# ecocar_CVM_V2.net
KiCad netlist of a schematic drawn in EAGLE
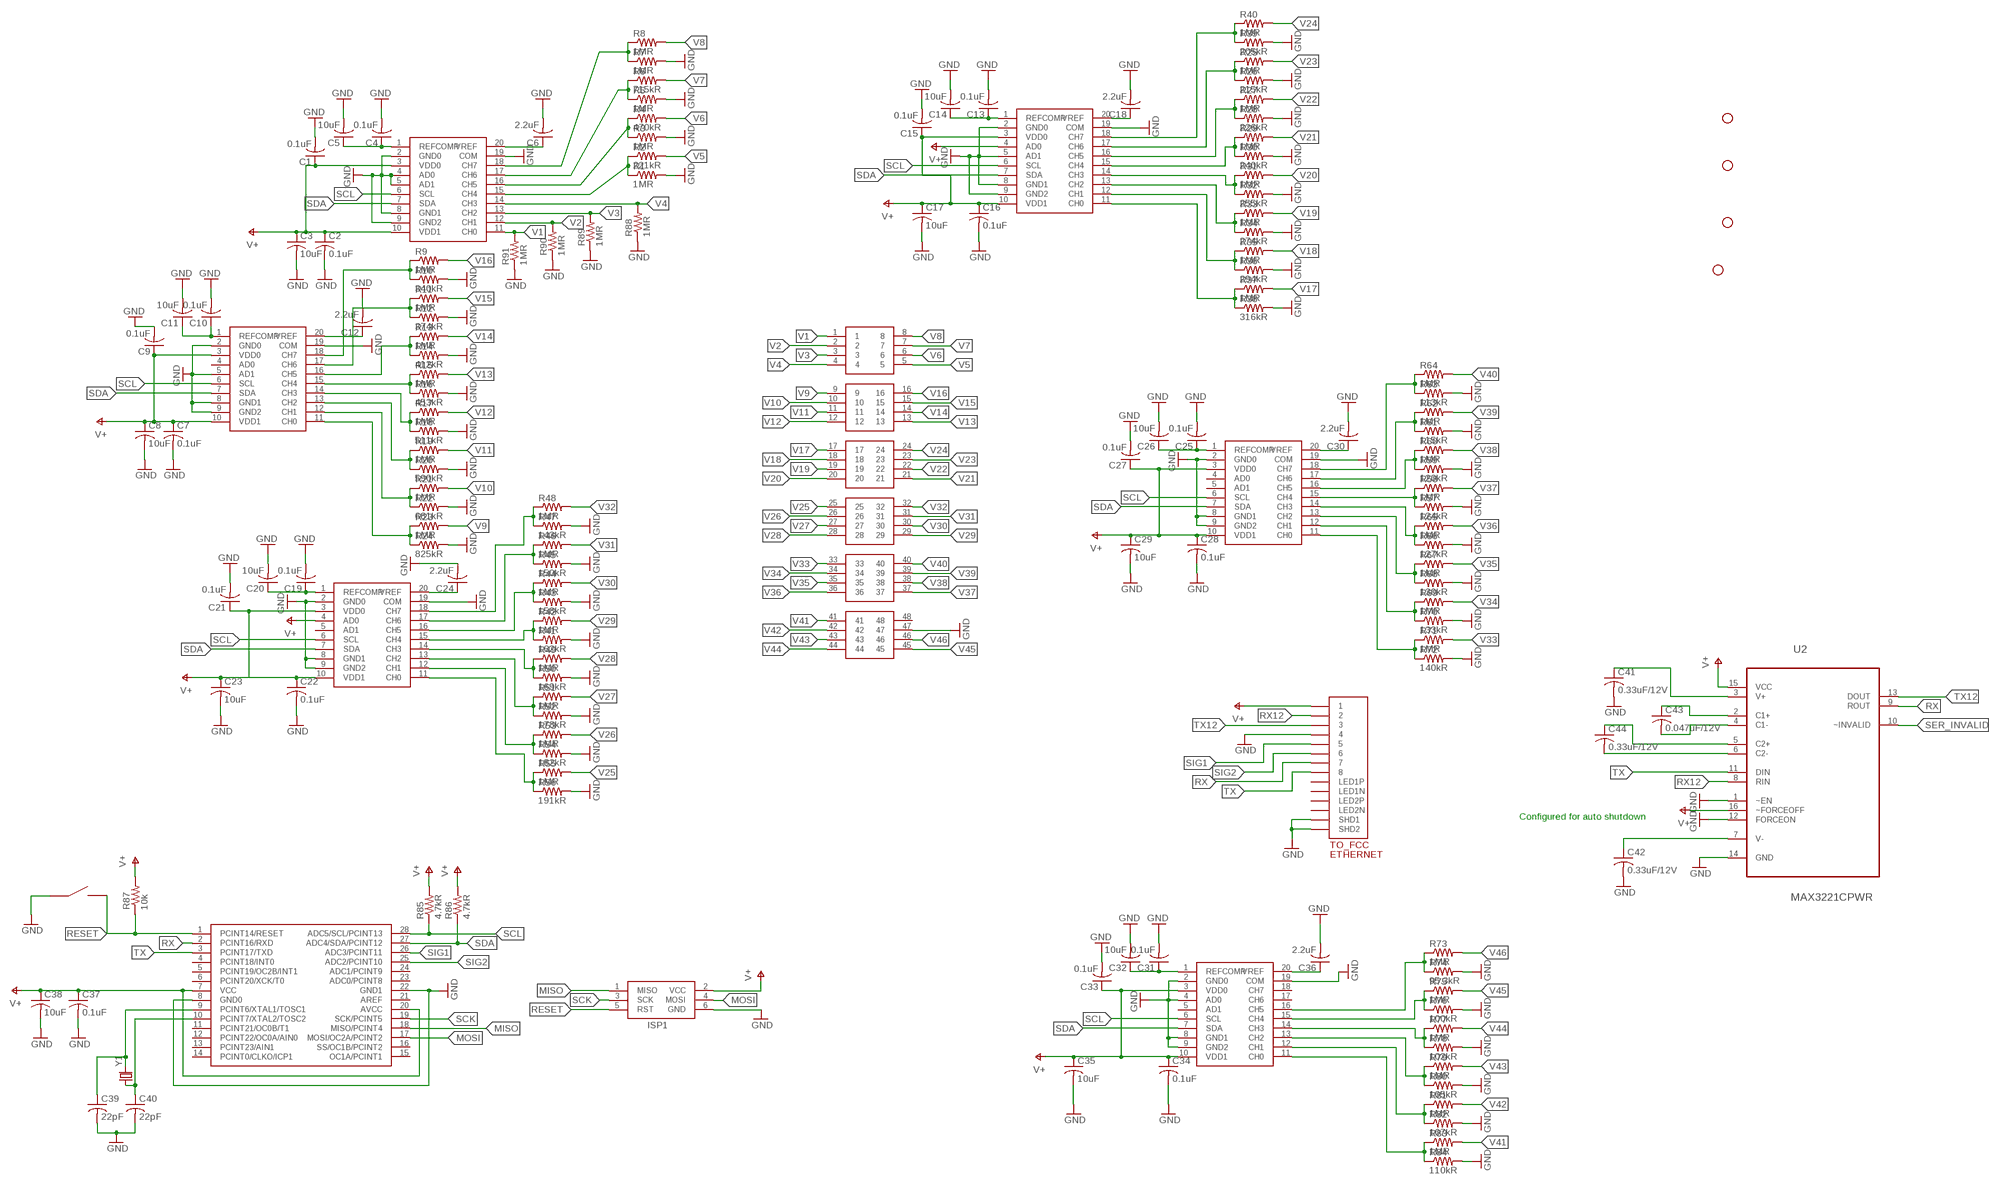
[diagram p0: schematic, sheet 1]

(export (version "E")
  (design (tool "Eeschema 10.0.6"))
  (components
    (comp (ref "0001000")
      (value "LTC2309")
      (footprint "eagle-import:TSSOP20")
      (libsource (lib "eagle-import") (part "LTC2309HF#PBF"))
    )
    (comp (ref "0001001")
      (value "LTC2309")
      (footprint "eagle-import:TSSOP20")
      (libsource (lib "eagle-import") (part "LTC2309HF#PBF"))
    )
    (comp (ref "0001010")
      (value "LTC2309")
      (footprint "eagle-import:TSSOP20")
      (libsource (lib "eagle-import") (part "LTC2309HF#PBF"))
    )
    (comp (ref "0001011")
      (value "LTC2309")
      (footprint "eagle-import:TSSOP20")
      (libsource (lib "eagle-import") (part "LTC2309HF#PBF"))
    )
    (comp (ref "0011000")
      (value "LTC2309")
      (footprint "eagle-import:TSSOP20")
      (libsource (lib "eagle-import") (part "LTC2309HF#PBF"))
    )
    (comp (ref "0011001")
      (value "LTC2309")
      (footprint "eagle-import:TSSOP20")
      (libsource (lib "eagle-import") (part "LTC2309HF#PBF"))
    )
    (comp (ref "C1")
      (value "0.1uF")
      (footprint "eagle-import:C0805")
      (libsource (lib "eagle-import") (part "rcl_C-USC0805"))
    )
    (comp (ref "C2")
      (value "0.1uF")
      (footprint "eagle-import:C0805")
      (libsource (lib "eagle-import") (part "rcl_C-USC0805"))
    )
    (comp (ref "C3")
      (value "10uF")
      (footprint "eagle-import:C0805")
      (libsource (lib "eagle-import") (part "rcl_C-USC0805"))
    )
    (comp (ref "C4")
      (value "0.1uF")
      (footprint "eagle-import:C0805")
      (libsource (lib "eagle-import") (part "rcl_C-USC0805"))
    )
    (comp (ref "C5")
      (value "10uF")
      (footprint "eagle-import:C0805")
      (libsource (lib "eagle-import") (part "rcl_C-USC0805"))
    )
    (comp (ref "C6")
      (value "2.2uF")
      (footprint "eagle-import:C0805")
      (libsource (lib "eagle-import") (part "rcl_C-USC0805"))
    )
    (comp (ref "C7")
      (value "0.1uF")
      (footprint "eagle-import:C0805")
      (libsource (lib "eagle-import") (part "rcl_C-USC0805"))
    )
    (comp (ref "C8")
      (value "10uF")
      (footprint "eagle-import:C0805")
      (libsource (lib "eagle-import") (part "rcl_C-USC0805"))
    )
    (comp (ref "C9")
      (value "0.1uF")
      (footprint "eagle-import:C0805")
      (libsource (lib "eagle-import") (part "rcl_C-USC0805"))
    )
    (comp (ref "C10")
      (value "0.1uF")
      (footprint "eagle-import:C0805")
      (libsource (lib "eagle-import") (part "rcl_C-USC0805"))
    )
    (comp (ref "C11")
      (value "10uF")
      (footprint "eagle-import:C0805")
      (libsource (lib "eagle-import") (part "rcl_C-USC0805"))
    )
    (comp (ref "C12")
      (value "2.2uF")
      (footprint "eagle-import:C0805")
      (libsource (lib "eagle-import") (part "rcl_C-USC0805"))
    )
    (comp (ref "C13")
      (value "0.1uF")
      (footprint "eagle-import:C0805")
      (libsource (lib "eagle-import") (part "rcl_C-USC0805"))
    )
    (comp (ref "C14")
      (value "10uF")
      (footprint "eagle-import:C0805")
      (libsource (lib "eagle-import") (part "rcl_C-USC0805"))
    )
    (comp (ref "C15")
      (value "0.1uF")
      (footprint "eagle-import:C0805")
      (libsource (lib "eagle-import") (part "rcl_C-USC0805"))
    )
    (comp (ref "C16")
      (value "0.1uF")
      (footprint "eagle-import:C0805")
      (libsource (lib "eagle-import") (part "rcl_C-USC0805"))
    )
    (comp (ref "C17")
      (value "10uF")
      (footprint "eagle-import:C0805")
      (libsource (lib "eagle-import") (part "rcl_C-USC0805"))
    )
    (comp (ref "C18")
      (value "2.2uF")
      (footprint "eagle-import:C0805")
      (libsource (lib "eagle-import") (part "rcl_C-USC0805"))
    )
    (comp (ref "C19")
      (value "0.1uF")
      (footprint "eagle-import:C0805")
      (libsource (lib "eagle-import") (part "rcl_C-USC0805"))
    )
    (comp (ref "C20")
      (value "10uF")
      (footprint "eagle-import:C0805")
      (libsource (lib "eagle-import") (part "rcl_C-USC0805"))
    )
    (comp (ref "C21")
      (value "0.1uF")
      (footprint "eagle-import:C0805")
      (libsource (lib "eagle-import") (part "rcl_C-USC0805"))
    )
    (comp (ref "C22")
      (value "0.1uF")
      (footprint "eagle-import:C0805")
      (libsource (lib "eagle-import") (part "rcl_C-USC0805"))
    )
    (comp (ref "C23")
      (value "10uF")
      (footprint "eagle-import:C0805")
      (libsource (lib "eagle-import") (part "rcl_C-USC0805"))
    )
    (comp (ref "C24")
      (value "2.2uF")
      (footprint "eagle-import:C0805")
      (libsource (lib "eagle-import") (part "rcl_C-USC0805"))
    )
    (comp (ref "C25")
      (value "0.1uF")
      (footprint "eagle-import:C0805")
      (libsource (lib "eagle-import") (part "rcl_C-USC0805"))
    )
    (comp (ref "C26")
      (value "10uF")
      (footprint "eagle-import:C0805")
      (libsource (lib "eagle-import") (part "rcl_C-USC0805"))
    )
    (comp (ref "C27")
      (value "0.1uF")
      (footprint "eagle-import:C0805")
      (libsource (lib "eagle-import") (part "rcl_C-USC0805"))
    )
    (comp (ref "C28")
      (value "0.1uF")
      (footprint "eagle-import:C0805")
      (libsource (lib "eagle-import") (part "rcl_C-USC0805"))
    )
    (comp (ref "C29")
      (value "10uF")
      (footprint "eagle-import:C0805")
      (libsource (lib "eagle-import") (part "rcl_C-USC0805"))
    )
    (comp (ref "C30")
      (value "2.2uF")
      (footprint "eagle-import:C0805")
      (libsource (lib "eagle-import") (part "rcl_C-USC0805"))
    )
    (comp (ref "C31")
      (value "0.1uF")
      (footprint "eagle-import:C0805")
      (libsource (lib "eagle-import") (part "rcl_C-USC0805"))
    )
    (comp (ref "C32")
      (value "10uF")
      (footprint "eagle-import:C0805")
      (libsource (lib "eagle-import") (part "rcl_C-USC0805"))
    )
    (comp (ref "C33")
      (value "0.1uF")
      (footprint "eagle-import:C0805")
      (libsource (lib "eagle-import") (part "rcl_C-USC0805"))
    )
    (comp (ref "C34")
      (value "0.1uF")
      (footprint "eagle-import:C0805")
      (libsource (lib "eagle-import") (part "rcl_C-USC0805"))
    )
    (comp (ref "C35")
      (value "10uF")
      (footprint "eagle-import:C0805")
      (libsource (lib "eagle-import") (part "rcl_C-USC0805"))
    )
    (comp (ref "C36")
      (value "2.2uF")
      (footprint "eagle-import:C0805")
      (libsource (lib "eagle-import") (part "rcl_C-USC0805"))
    )
    (comp (ref "C37")
      (value "0.1uF")
      (footprint "eagle-import:C0805")
      (libsource (lib "eagle-import") (part "rcl_C-USC0805"))
    )
    (comp (ref "C38")
      (value "10uF")
      (footprint "eagle-import:C0805")
      (libsource (lib "eagle-import") (part "rcl_C-USC0805"))
    )
    (comp (ref "C39")
      (value "22pF")
      (footprint "eagle-import:C0805")
      (libsource (lib "eagle-import") (part "rcl_C-USC0805"))
    )
    (comp (ref "C40")
      (value "22pF")
      (footprint "eagle-import:C0805")
      (libsource (lib "eagle-import") (part "rcl_C-USC0805"))
    )
    (comp (ref "C41")
      (value "0.33uF/12V")
      (footprint "eagle-import:C0805")
      (libsource (lib "eagle-import") (part "C-USC0805"))
    )
    (comp (ref "C42")
      (value "0.33uF/12V")
      (footprint "eagle-import:C0805")
      (libsource (lib "eagle-import") (part "C-USC0805"))
    )
    (comp (ref "C43")
      (value "0.047uF/12V")
      (footprint "eagle-import:C0805")
      (libsource (lib "eagle-import") (part "C-USC0805"))
    )
    (comp (ref "C44")
      (value "0.33uF/12V")
      (footprint "eagle-import:C0805")
      (libsource (lib "eagle-import") (part "C-USC0805"))
    )
    (comp (ref "ISP1")
      (value "AVRISP-BOX")
      (footprint "eagle-import:AVRISP-BOX")
      (libsource (lib "eagle-import") (part "AVRISP-BOX"))
    )
    (comp (ref "R1")
      (value "1MR")
      (footprint "eagle-import:R0805")
      (libsource (lib "eagle-import") (part "R-US_R0805"))
    )
    (comp (ref "R2")
      (value "221kR")
      (footprint "eagle-import:R0805")
      (libsource (lib "eagle-import") (part "R-US_R0805"))
    )
    (comp (ref "R3")
      (value "1MR")
      (footprint "eagle-import:R0805")
      (libsource (lib "eagle-import") (part "R-US_R0805"))
    )
    (comp (ref "R4")
      (value "470kR")
      (footprint "eagle-import:R0805")
      (libsource (lib "eagle-import") (part "R-US_R0805"))
    )
    (comp (ref "R5")
      (value "1MR")
      (footprint "eagle-import:R0805")
      (libsource (lib "eagle-import") (part "R-US_R0805"))
    )
    (comp (ref "R6")
      (value "715kR")
      (footprint "eagle-import:R0805")
      (libsource (lib "eagle-import") (part "R-US_R0805"))
    )
    (comp (ref "R7")
      (value "1MR")
      (footprint "eagle-import:R0805")
      (libsource (lib "eagle-import") (part "R-US_R0805"))
    )
    (comp (ref "R8")
      (value "1MR")
      (footprint "eagle-import:R0805")
      (libsource (lib "eagle-import") (part "R-US_R0805"))
    )
    (comp (ref "R9")
      (value "1MR")
      (footprint "eagle-import:R0805")
      (libsource (lib "eagle-import") (part "R-US_R0805"))
    )
    (comp (ref "R10")
      (value "340kR")
      (footprint "eagle-import:R0805")
      (libsource (lib "eagle-import") (part "R-US_R0805"))
    )
    (comp (ref "R11")
      (value "1MR")
      (footprint "eagle-import:R0805")
      (libsource (lib "eagle-import") (part "R-US_R0805"))
    )
    (comp (ref "R12")
      (value "374kR")
      (footprint "eagle-import:R0805")
      (libsource (lib "eagle-import") (part "R-US_R0805"))
    )
    (comp (ref "R13")
      (value "1MR")
      (footprint "eagle-import:R0805")
      (libsource (lib "eagle-import") (part "R-US_R0805"))
    )
    (comp (ref "R14")
      (value "412kR")
      (footprint "eagle-import:R0805")
      (libsource (lib "eagle-import") (part "R-US_R0805"))
    )
    (comp (ref "R15")
      (value "1MR")
      (footprint "eagle-import:R0805")
      (libsource (lib "eagle-import") (part "R-US_R0805"))
    )
    (comp (ref "R16")
      (value "453kR")
      (footprint "eagle-import:R0805")
      (libsource (lib "eagle-import") (part "R-US_R0805"))
    )
    (comp (ref "R17")
      (value "1MR")
      (footprint "eagle-import:R0805")
      (libsource (lib "eagle-import") (part "R-US_R0805"))
    )
    (comp (ref "R18")
      (value "511kR")
      (footprint "eagle-import:R0805")
      (libsource (lib "eagle-import") (part "R-US_R0805"))
    )
    (comp (ref "R19")
      (value "1MR")
      (footprint "eagle-import:R0805")
      (libsource (lib "eagle-import") (part "R-US_R0805"))
    )
    (comp (ref "R20")
      (value "590kR")
      (footprint "eagle-import:R0805")
      (libsource (lib "eagle-import") (part "R-US_R0805"))
    )
    (comp (ref "R21")
      (value "1MR")
      (footprint "eagle-import:R0805")
      (libsource (lib "eagle-import") (part "R-US_R0805"))
    )
    (comp (ref "R22")
      (value "681kR")
      (footprint "eagle-import:R0805")
      (libsource (lib "eagle-import") (part "R-US_R0805"))
    )
    (comp (ref "R23")
      (value "1MR")
      (footprint "eagle-import:R0805")
      (libsource (lib "eagle-import") (part "R-US_R0805"))
    )
    (comp (ref "R24")
      (value "825kR")
      (footprint "eagle-import:R0805")
      (libsource (lib "eagle-import") (part "R-US_R0805"))
    )
    (comp (ref "R25")
      (value "1MR")
      (footprint "eagle-import:R0805")
      (libsource (lib "eagle-import") (part "R-US_R0805"))
    )
    (comp (ref "R26")
      (value "215kR")
      (footprint "eagle-import:R0805")
      (libsource (lib "eagle-import") (part "R-US_R0805"))
    )
    (comp (ref "R27")
      (value "1MR")
      (footprint "eagle-import:R0805")
      (libsource (lib "eagle-import") (part "R-US_R0805"))
    )
    (comp (ref "R28")
      (value "226kR")
      (footprint "eagle-import:R0805")
      (libsource (lib "eagle-import") (part "R-US_R0805"))
    )
    (comp (ref "R29")
      (value "1MR")
      (footprint "eagle-import:R0805")
      (libsource (lib "eagle-import") (part "R-US_R0805"))
    )
    (comp (ref "R30")
      (value "240kR")
      (footprint "eagle-import:R0805")
      (libsource (lib "eagle-import") (part "R-US_R0805"))
    )
    (comp (ref "R31")
      (value "1MR")
      (footprint "eagle-import:R0805")
      (libsource (lib "eagle-import") (part "R-US_R0805"))
    )
    (comp (ref "R32")
      (value "255kR")
      (footprint "eagle-import:R0805")
      (libsource (lib "eagle-import") (part "R-US_R0805"))
    )
    (comp (ref "R33")
      (value "1MR")
      (footprint "eagle-import:R0805")
      (libsource (lib "eagle-import") (part "R-US_R0805"))
    )
    (comp (ref "R34")
      (value "274kR")
      (footprint "eagle-import:R0805")
      (libsource (lib "eagle-import") (part "R-US_R0805"))
    )
    (comp (ref "R35")
      (value "1MR")
      (footprint "eagle-import:R0805")
      (libsource (lib "eagle-import") (part "R-US_R0805"))
    )
    (comp (ref "R36")
      (value "294kR")
      (footprint "eagle-import:R0805")
      (libsource (lib "eagle-import") (part "R-US_R0805"))
    )
    (comp (ref "R37")
      (value "1MR")
      (footprint "eagle-import:R0805")
      (libsource (lib "eagle-import") (part "R-US_R0805"))
    )
    (comp (ref "R38")
      (value "316kR")
      (footprint "eagle-import:R0805")
      (libsource (lib "eagle-import") (part "R-US_R0805"))
    )
    (comp (ref "R39")
      (value "205kR")
      (footprint "eagle-import:R0805")
      (libsource (lib "eagle-import") (part "R-US_R0805"))
    )
    (comp (ref "R40")
      (value "1MR")
      (footprint "eagle-import:R0805")
      (libsource (lib "eagle-import") (part "R-US_R0805"))
    )
    (comp (ref "R41")
      (value "162kR")
      (footprint "eagle-import:R0805")
      (libsource (lib "eagle-import") (part "R-US_R0805"))
    )
    (comp (ref "R42")
      (value "1MR")
      (footprint "eagle-import:R0805")
      (libsource (lib "eagle-import") (part "R-US_R0805"))
    )
    (comp (ref "R43")
      (value "158kR")
      (footprint "eagle-import:R0805")
      (libsource (lib "eagle-import") (part "R-US_R0805"))
    )
    (comp (ref "R44")
      (value "1MR")
      (footprint "eagle-import:R0805")
      (libsource (lib "eagle-import") (part "R-US_R0805"))
    )
    (comp (ref "R45")
      (value "150kR")
      (footprint "eagle-import:R0805")
      (libsource (lib "eagle-import") (part "R-US_R0805"))
    )
    (comp (ref "R46")
      (value "1MR")
      (footprint "eagle-import:R0805")
      (libsource (lib "eagle-import") (part "R-US_R0805"))
    )
    (comp (ref "R47")
      (value "143kR")
      (footprint "eagle-import:R0805")
      (libsource (lib "eagle-import") (part "R-US_R0805"))
    )
    (comp (ref "R48")
      (value "1MR")
      (footprint "eagle-import:R0805")
      (libsource (lib "eagle-import") (part "R-US_R0805"))
    )
    (comp (ref "R49")
      (value "1MR")
      (footprint "eagle-import:R0805")
      (libsource (lib "eagle-import") (part "R-US_R0805"))
    )
    (comp (ref "R50")
      (value "169kR")
      (footprint "eagle-import:R0805")
      (libsource (lib "eagle-import") (part "R-US_R0805"))
    )
    (comp (ref "R51")
      (value "1MR")
      (footprint "eagle-import:R0805")
      (libsource (lib "eagle-import") (part "R-US_R0805"))
    )
    (comp (ref "R52")
      (value "178kR")
      (footprint "eagle-import:R0805")
      (libsource (lib "eagle-import") (part "R-US_R0805"))
    )
    (comp (ref "R53")
      (value "1MR")
      (footprint "eagle-import:R0805")
      (libsource (lib "eagle-import") (part "R-US_R0805"))
    )
    (comp (ref "R54")
      (value "182kR")
      (footprint "eagle-import:R0805")
      (libsource (lib "eagle-import") (part "R-US_R0805"))
    )
    (comp (ref "R55")
      (value "1MR")
      (footprint "eagle-import:R0805")
      (libsource (lib "eagle-import") (part "R-US_R0805"))
    )
    (comp (ref "R56")
      (value "191kR")
      (footprint "eagle-import:R0805")
      (libsource (lib "eagle-import") (part "R-US_R0805"))
    )
    (comp (ref "R57")
      (value "124kR")
      (footprint "eagle-import:R0805")
      (libsource (lib "eagle-import") (part "R-US_R0805"))
    )
    (comp (ref "R58")
      (value "1MR")
      (footprint "eagle-import:R0805")
      (libsource (lib "eagle-import") (part "R-US_R0805"))
    )
    (comp (ref "R59")
      (value "120kR")
      (footprint "eagle-import:R0805")
      (libsource (lib "eagle-import") (part "R-US_R0805"))
    )
    (comp (ref "R60")
      (value "1MR")
      (footprint "eagle-import:R0805")
      (libsource (lib "eagle-import") (part "R-US_R0805"))
    )
    (comp (ref "R61")
      (value "115kR")
      (footprint "eagle-import:R0805")
      (libsource (lib "eagle-import") (part "R-US_R0805"))
    )
    (comp (ref "R62")
      (value "1MR")
      (footprint "eagle-import:R0805")
      (libsource (lib "eagle-import") (part "R-US_R0805"))
    )
    (comp (ref "R63")
      (value "113kR")
      (footprint "eagle-import:R0805")
      (libsource (lib "eagle-import") (part "R-US_R0805"))
    )
    (comp (ref "R64")
      (value "1MR")
      (footprint "eagle-import:R0805")
      (libsource (lib "eagle-import") (part "R-US_R0805"))
    )
    (comp (ref "R65")
      (value "1MR")
      (footprint "eagle-import:R0805")
      (libsource (lib "eagle-import") (part "R-US_R0805"))
    )
    (comp (ref "R66")
      (value "127kR")
      (footprint "eagle-import:R0805")
      (libsource (lib "eagle-import") (part "R-US_R0805"))
    )
    (comp (ref "R67")
      (value "1MR")
      (footprint "eagle-import:R0805")
      (libsource (lib "eagle-import") (part "R-US_R0805"))
    )
    (comp (ref "R68")
      (value "130kR")
      (footprint "eagle-import:R0805")
      (libsource (lib "eagle-import") (part "R-US_R0805"))
    )
    (comp (ref "R69")
      (value "1MR")
      (footprint "eagle-import:R0805")
      (libsource (lib "eagle-import") (part "R-US_R0805"))
    )
    (comp (ref "R70")
      (value "133kR")
      (footprint "eagle-import:R0805")
      (libsource (lib "eagle-import") (part "R-US_R0805"))
    )
    (comp (ref "R71")
      (value "1MR")
      (footprint "eagle-import:R0805")
      (libsource (lib "eagle-import") (part "R-US_R0805"))
    )
    (comp (ref "R72")
      (value "140kR")
      (footprint "eagle-import:R0805")
      (libsource (lib "eagle-import") (part "R-US_R0805"))
    )
    (comp (ref "R73")
      (value "1MR")
      (footprint "eagle-import:R0805")
      (libsource (lib "eagle-import") (part "R-US_R0805"))
    )
    (comp (ref "R74")
      (value "95.3kR")
      (footprint "eagle-import:R0805")
      (libsource (lib "eagle-import") (part "R-US_R0805"))
    )
    (comp (ref "R75")
      (value "1MR")
      (footprint "eagle-import:R0805")
      (libsource (lib "eagle-import") (part "R-US_R0805"))
    )
    (comp (ref "R76")
      (value "100kR")
      (footprint "eagle-import:R0805")
      (libsource (lib "eagle-import") (part "R-US_R0805"))
    )
    (comp (ref "R77")
      (value "1MR")
      (footprint "eagle-import:R0805")
      (libsource (lib "eagle-import") (part "R-US_R0805"))
    )
    (comp (ref "R78")
      (value "102kR")
      (footprint "eagle-import:R0805")
      (libsource (lib "eagle-import") (part "R-US_R0805"))
    )
    (comp (ref "R79")
      (value "1MR")
      (footprint "eagle-import:R0805")
      (libsource (lib "eagle-import") (part "R-US_R0805"))
    )
    (comp (ref "R80")
      (value "105kR")
      (footprint "eagle-import:R0805")
      (libsource (lib "eagle-import") (part "R-US_R0805"))
    )
    (comp (ref "R81")
      (value "1MR")
      (footprint "eagle-import:R0805")
      (libsource (lib "eagle-import") (part "R-US_R0805"))
    )
    (comp (ref "R82")
      (value "107kR")
      (footprint "eagle-import:R0805")
      (libsource (lib "eagle-import") (part "R-US_R0805"))
    )
    (comp (ref "R83")
      (value "1MR")
      (footprint "eagle-import:R0805")
      (libsource (lib "eagle-import") (part "R-US_R0805"))
    )
    (comp (ref "R84")
      (value "110kR")
      (footprint "eagle-import:R0805")
      (libsource (lib "eagle-import") (part "R-US_R0805"))
    )
    (comp (ref "R85")
      (value "4.7kR")
      (footprint "eagle-import:R0805")
      (libsource (lib "eagle-import") (part "R-US_R0805"))
    )
    (comp (ref "R86")
      (value "4.7kR")
      (footprint "eagle-import:R0805")
      (libsource (lib "eagle-import") (part "R-US_R0805"))
    )
    (comp (ref "R87")
      (value "10k")
      (footprint "eagle-import:R0805")
      (libsource (lib "eagle-import") (part "R-US_R0805"))
    )
    (comp (ref "R88")
      (value "1MR")
      (footprint "eagle-import:R0805")
      (libsource (lib "eagle-import") (part "R-US_R0805"))
    )
    (comp (ref "R89")
      (value "1MR")
      (footprint "eagle-import:R0805")
      (libsource (lib "eagle-import") (part "R-US_R0805"))
    )
    (comp (ref "R90")
      (value "1MR")
      (footprint "eagle-import:R0805")
      (libsource (lib "eagle-import") (part "R-US_R0805"))
    )
    (comp (ref "R91")
      (value "1MR")
      (footprint "eagle-import:R0805")
      (libsource (lib "eagle-import") (part "R-US_R0805"))
    )
    (comp (ref "RESET_BTN")
      (value "EG4621CT-ND")
      (footprint "eagle-import:EG4621CT-ND")
      (libsource (lib "eagle-import") (part "EG4621CT-ND"))
    )
    (comp (ref "STANDOFF1")
      (value "STAND-OFF")
      (footprint "eagle-import:STAND-OFF")
      (libsource (lib "eagle-import") (part "STAND-OFF"))
    )
    (comp (ref "STANDOFF2")
      (value "STAND-OFF")
      (footprint "eagle-import:STAND-OFF")
      (libsource (lib "eagle-import") (part "STAND-OFF"))
    )
    (comp (ref "STANDOFF3")
      (value "STAND-OFF")
      (footprint "eagle-import:STAND-OFF")
      (libsource (lib "eagle-import") (part "STAND-OFF"))
    )
    (comp (ref "STANDOFF4")
      (value "STAND-OFF")
      (footprint "eagle-import:STAND-OFF")
      (libsource (lib "eagle-import") (part "STAND-OFF"))
    )
    (comp (ref "TO_FCC")
      (value "ETHERNET")
      (footprint "eagle-import:A122645-ND")
      (libsource (lib "eagle-import") (part "ETHERNET"))
    )
    (comp (ref "U$1")
      (value "ATMEGA328P")
      (footprint "eagle-import:DIL28-3")
      (libsource (lib "eagle-import") (part "ATMEGA328P"))
    )
    (comp (ref "U$3")
      (value "6-RJ45")
      (footprint "eagle-import:48-PIN-THROUGHHOLE")
      (libsource (lib "eagle-import") (part "6-RJ45-5557572-3"))
    )
    (comp (ref "U2")
      (value "MAX3221CPWR")
      (footprint "eagle-import:SOP65P640X120-16N")
      (libsource (lib "eagle-import") (part "MAX3221CPWR"))
    )
    (comp (ref "Y1")
      (value "CRYSTALHC49US")
      (footprint "eagle-import:HC49US")
      (libsource (lib "eagle-import") (part "CRYSTALHC49US"))
    )
  )
  (nets
    (net (code "1") (name "GND") (class "Default")
      (node (ref "0001000") (pin "19") (pinfunction "COM_19") (pintype "bidirectional"))
      (node (ref "0001000") (pin "2") (pinfunction "GND0_2") (pintype "bidirectional"))
      (node (ref "0001000") (pin "4") (pinfunction "AD0_4") (pintype "bidirectional"))
      (node (ref "0001000") (pin "5") (pinfunction "AD1_5") (pintype "bidirectional"))
      (node (ref "0001000") (pin "8") (pinfunction "GND1_8") (pintype "bidirectional"))
      (node (ref "0001000") (pin "9") (pinfunction "GND2_9") (pintype "bidirectional"))
      (node (ref "0001001") (pin "19") (pinfunction "COM_19") (pintype "bidirectional"))
      (node (ref "0001001") (pin "2") (pinfunction "GND0_2") (pintype "bidirectional"))
      (node (ref "0001001") (pin "5") (pinfunction "AD1_5") (pintype "bidirectional"))
      (node (ref "0001001") (pin "8") (pinfunction "GND1_8") (pintype "bidirectional"))
      (node (ref "0001001") (pin "9") (pinfunction "GND2_9") (pintype "bidirectional"))
      (node (ref "0001010") (pin "19") (pinfunction "COM_19") (pintype "bidirectional"))
      (node (ref "0001010") (pin "2") (pinfunction "GND0_2") (pintype "bidirectional"))
      (node (ref "0001010") (pin "5") (pinfunction "AD1_5") (pintype "bidirectional"))
      (node (ref "0001010") (pin "8") (pinfunction "GND1_8") (pintype "bidirectional"))
      (node (ref "0001010") (pin "9") (pinfunction "GND2_9") (pintype "bidirectional"))
      (node (ref "0001011") (pin "19") (pinfunction "COM_19") (pintype "bidirectional"))
      (node (ref "0001011") (pin "2") (pinfunction "GND0_2") (pintype "bidirectional"))
      (node (ref "0001011") (pin "8") (pinfunction "GND1_8") (pintype "bidirectional"))
      (node (ref "0001011") (pin "9") (pinfunction "GND2_9") (pintype "bidirectional"))
      (node (ref "0011000") (pin "19") (pinfunction "COM_19") (pintype "bidirectional"))
      (node (ref "0011000") (pin "2") (pinfunction "GND0_2") (pintype "bidirectional"))
      (node (ref "0011000") (pin "8") (pinfunction "GND1_8") (pintype "bidirectional"))
      (node (ref "0011000") (pin "9") (pinfunction "GND2_9") (pintype "bidirectional"))
      (node (ref "0011001") (pin "19") (pinfunction "COM_19") (pintype "bidirectional"))
      (node (ref "0011001") (pin "2") (pinfunction "GND0_2") (pintype "bidirectional"))
      (node (ref "0011001") (pin "4") (pinfunction "AD0_4") (pintype "bidirectional"))
      (node (ref "0011001") (pin "8") (pinfunction "GND1_8") (pintype "bidirectional"))
      (node (ref "0011001") (pin "9") (pinfunction "GND2_9") (pintype "bidirectional"))
      (node (ref "C1") (pin "2") (pinfunction "2_2") (pintype "passive"))
      (node (ref "C10") (pin "2") (pinfunction "2_2") (pintype "passive"))
      (node (ref "C11") (pin "2") (pinfunction "2_2") (pintype "passive"))
      (node (ref "C12") (pin "2") (pinfunction "2_2") (pintype "passive"))
      (node (ref "C13") (pin "2") (pinfunction "2_2") (pintype "passive"))
      (node (ref "C14") (pin "2") (pinfunction "2_2") (pintype "passive"))
      (node (ref "C15") (pin "2") (pinfunction "2_2") (pintype "passive"))
      (node (ref "C16") (pin "2") (pinfunction "2_2") (pintype "passive"))
      (node (ref "C17") (pin "2") (pinfunction "2_2") (pintype "passive"))
      (node (ref "C18") (pin "2") (pinfunction "2_2") (pintype "passive"))
      (node (ref "C19") (pin "2") (pinfunction "2_2") (pintype "passive"))
      (node (ref "C2") (pin "2") (pinfunction "2_2") (pintype "passive"))
      (node (ref "C20") (pin "2") (pinfunction "2_2") (pintype "passive"))
      (node (ref "C21") (pin "2") (pinfunction "2_2") (pintype "passive"))
      (node (ref "C22") (pin "2") (pinfunction "2_2") (pintype "passive"))
      (node (ref "C23") (pin "2") (pinfunction "2_2") (pintype "passive"))
      (node (ref "C24") (pin "2") (pinfunction "2_2") (pintype "passive"))
      (node (ref "C25") (pin "2") (pinfunction "2_2") (pintype "passive"))
      (node (ref "C26") (pin "2") (pinfunction "2_2") (pintype "passive"))
      (node (ref "C27") (pin "2") (pinfunction "2_2") (pintype "passive"))
      (node (ref "C28") (pin "2") (pinfunction "2_2") (pintype "passive"))
      (node (ref "C29") (pin "2") (pinfunction "2_2") (pintype "passive"))
      (node (ref "C3") (pin "2") (pinfunction "2_2") (pintype "passive"))
      (node (ref "C30") (pin "2") (pinfunction "2_2") (pintype "passive"))
      (node (ref "C31") (pin "2") (pinfunction "2_2") (pintype "passive"))
      (node (ref "C32") (pin "2") (pinfunction "2_2") (pintype "passive"))
      (node (ref "C33") (pin "2") (pinfunction "2_2") (pintype "passive"))
      (node (ref "C34") (pin "2") (pinfunction "2_2") (pintype "passive"))
      (node (ref "C35") (pin "2") (pinfunction "2_2") (pintype "passive"))
      (node (ref "C36") (pin "2") (pinfunction "2_2") (pintype "passive"))
      (node (ref "C37") (pin "2") (pinfunction "2_2") (pintype "passive"))
      (node (ref "C38") (pin "2") (pinfunction "2_2") (pintype "passive"))
      (node (ref "C39") (pin "2") (pinfunction "2_2") (pintype "passive"))
      (node (ref "C4") (pin "2") (pinfunction "2_2") (pintype "passive"))
      (node (ref "C40") (pin "2") (pinfunction "2_2") (pintype "passive"))
      (node (ref "C41") (pin "2") (pinfunction "2_2") (pintype "passive"))
      (node (ref "C42") (pin "2") (pinfunction "2_2") (pintype "passive"))
      (node (ref "C5") (pin "2") (pinfunction "2_2") (pintype "passive"))
      (node (ref "C6") (pin "2") (pinfunction "2_2") (pintype "passive"))
      (node (ref "C7") (pin "2") (pinfunction "2_2") (pintype "passive"))
      (node (ref "C8") (pin "2") (pinfunction "2_2") (pintype "passive"))
      (node (ref "C9") (pin "2") (pinfunction "2_2") (pintype "passive"))
      (node (ref "ISP1") (pin "6") (pinfunction "GND_6") (pintype "power_in"))
      (node (ref "R1") (pin "2") (pinfunction "2_2") (pintype "passive"))
      (node (ref "R10") (pin "2") (pinfunction "2_2") (pintype "passive"))
      (node (ref "R12") (pin "2") (pinfunction "2_2") (pintype "passive"))
      (node (ref "R14") (pin "2") (pinfunction "2_2") (pintype "passive"))
      (node (ref "R16") (pin "2") (pinfunction "2_2") (pintype "passive"))
      (node (ref "R18") (pin "2") (pinfunction "2_2") (pintype "passive"))
      (node (ref "R20") (pin "2") (pinfunction "2_2") (pintype "passive"))
      (node (ref "R22") (pin "2") (pinfunction "2_2") (pintype "passive"))
      (node (ref "R24") (pin "2") (pinfunction "2_2") (pintype "passive"))
      (node (ref "R26") (pin "2") (pinfunction "2_2") (pintype "passive"))
      (node (ref "R28") (pin "2") (pinfunction "2_2") (pintype "passive"))
      (node (ref "R3") (pin "2") (pinfunction "2_2") (pintype "passive"))
      (node (ref "R30") (pin "2") (pinfunction "2_2") (pintype "passive"))
      (node (ref "R32") (pin "2") (pinfunction "2_2") (pintype "passive"))
      (node (ref "R34") (pin "2") (pinfunction "2_2") (pintype "passive"))
      (node (ref "R36") (pin "2") (pinfunction "2_2") (pintype "passive"))
      (node (ref "R38") (pin "2") (pinfunction "2_2") (pintype "passive"))
      (node (ref "R39") (pin "2") (pinfunction "2_2") (pintype "passive"))
      (node (ref "R41") (pin "2") (pinfunction "2_2") (pintype "passive"))
      (node (ref "R43") (pin "2") (pinfunction "2_2") (pintype "passive"))
      (node (ref "R45") (pin "2") (pinfunction "2_2") (pintype "passive"))
      (node (ref "R47") (pin "2") (pinfunction "2_2") (pintype "passive"))
      (node (ref "R5") (pin "2") (pinfunction "2_2") (pintype "passive"))
      (node (ref "R50") (pin "2") (pinfunction "2_2") (pintype "passive"))
      (node (ref "R52") (pin "2") (pinfunction "2_2") (pintype "passive"))
      (node (ref "R54") (pin "2") (pinfunction "2_2") (pintype "passive"))
      (node (ref "R56") (pin "2") (pinfunction "2_2") (pintype "passive"))
      (node (ref "R57") (pin "2") (pinfunction "2_2") (pintype "passive"))
      (node (ref "R59") (pin "2") (pinfunction "2_2") (pintype "passive"))
      (node (ref "R61") (pin "2") (pinfunction "2_2") (pintype "passive"))
      (node (ref "R63") (pin "2") (pinfunction "2_2") (pintype "passive"))
      (node (ref "R66") (pin "2") (pinfunction "2_2") (pintype "passive"))
      (node (ref "R68") (pin "2") (pinfunction "2_2") (pintype "passive"))
      (node (ref "R7") (pin "2") (pinfunction "2_2") (pintype "passive"))
      (node (ref "R70") (pin "2") (pinfunction "2_2") (pintype "passive"))
      (node (ref "R72") (pin "2") (pinfunction "2_2") (pintype "passive"))
      (node (ref "R74") (pin "2") (pinfunction "2_2") (pintype "passive"))
      (node (ref "R76") (pin "2") (pinfunction "2_2") (pintype "passive"))
      (node (ref "R78") (pin "2") (pinfunction "2_2") (pintype "passive"))
      (node (ref "R80") (pin "2") (pinfunction "2_2") (pintype "passive"))
      (node (ref "R82") (pin "2") (pinfunction "2_2") (pintype "passive"))
      (node (ref "R84") (pin "2") (pinfunction "2_2") (pintype "passive"))
      (node (ref "R88") (pin "1") (pinfunction "1_1") (pintype "passive"))
      (node (ref "R89") (pin "1") (pinfunction "1_1") (pintype "passive"))
      (node (ref "R90") (pin "1") (pinfunction "1_1") (pintype "passive"))
      (node (ref "R91") (pin "1") (pinfunction "1_1") (pintype "passive"))
      (node (ref "RESET_BTN") (pin "P$1") (pinfunction "P$1_P$1") (pintype "bidirectional"))
      (node (ref "RESET_BTN") (pin "P$2") (pinfunction "P$1_P$2") (pintype "bidirectional"))
      (node (ref "TO_FCC") (pin "P$13") (pinfunction "SHD1_P$13") (pintype "bidirectional"))
      (node (ref "TO_FCC") (pin "P$14") (pinfunction "SHD2_P$14") (pintype "bidirectional"))
      (node (ref "TO_FCC") (pin "P$4") (pinfunction "4_P$4") (pintype "bidirectional"))
      (node (ref "U$1") (pin "22") (pinfunction "GND1_22") (pintype "bidirectional"))
      (node (ref "U$1") (pin "8") (pinfunction "GND0_8") (pintype "bidirectional"))
      (node (ref "U$3") (pin "47") (pinfunction "47_47") (pintype "bidirectional"))
      (node (ref "U2") (pin "1") (pinfunction "~{EN}_1") (pintype "input"))
      (node (ref "U2") (pin "12") (pinfunction "FORCEON_12") (pintype "input"))
      (node (ref "U2") (pin "14") (pinfunction "GND_14") (pintype "passive"))
    )
    (net (code "2") (name "MISO") (class "Default")
      (node (ref "ISP1") (pin "1") (pinfunction "MISO_1") (pintype "input"))
      (node (ref "U$1") (pin "18") (pinfunction "MISO/PCINT4_18") (pintype "bidirectional"))
    )
    (net (code "3") (name "MOSI") (class "Default")
      (node (ref "ISP1") (pin "4") (pinfunction "MOSI_4") (pintype "output"))
      (node (ref "U$1") (pin "17") (pinfunction "MOSI/OC2A/PCINT2_17") (pintype "bidirectional"))
    )
    (net (code "4") (name "Net-(0001000-CH4)") (class "Default")
      (node (ref "0001000") (pin "15") (pinfunction "CH4_15") (pintype "bidirectional"))
      (node (ref "R1") (pin "1") (pinfunction "1_1") (pintype "passive"))
      (node (ref "R2") (pin "1") (pinfunction "1_1") (pintype "passive"))
    )
    (net (code "5") (name "Net-(0001000-CH5)") (class "Default")
      (node (ref "0001000") (pin "16") (pinfunction "CH5_16") (pintype "bidirectional"))
      (node (ref "R3") (pin "1") (pinfunction "1_1") (pintype "passive"))
      (node (ref "R4") (pin "1") (pinfunction "1_1") (pintype "passive"))
    )
    (net (code "6") (name "Net-(0001000-CH6)") (class "Default")
      (node (ref "0001000") (pin "17") (pinfunction "CH6_17") (pintype "bidirectional"))
      (node (ref "R5") (pin "1") (pinfunction "1_1") (pintype "passive"))
      (node (ref "R6") (pin "1") (pinfunction "1_1") (pintype "passive"))
    )
    (net (code "7") (name "Net-(0001000-CH7)") (class "Default")
      (node (ref "0001000") (pin "18") (pinfunction "CH7_18") (pintype "bidirectional"))
      (node (ref "R7") (pin "1") (pinfunction "1_1") (pintype "passive"))
      (node (ref "R8") (pin "1") (pinfunction "1_1") (pintype "passive"))
    )
    (net (code "8") (name "Net-(0001000-REFCOMP)") (class "Default")
      (node (ref "0001000") (pin "1") (pinfunction "REFCOMP_1") (pintype "bidirectional"))
      (node (ref "C4") (pin "1") (pinfunction "1_1") (pintype "passive"))
      (node (ref "C5") (pin "1") (pinfunction "1_1") (pintype "passive"))
    )
    (net (code "9") (name "Net-(0001000-VREF)") (class "Default")
      (node (ref "0001000") (pin "20") (pinfunction "VREF_20") (pintype "bidirectional"))
      (node (ref "C6") (pin "1") (pinfunction "1_1") (pintype "passive"))
    )
    (net (code "10") (name "Net-(0001001-CH0)") (class "Default")
      (node (ref "0001001") (pin "11") (pinfunction "CH0_11") (pintype "bidirectional"))
      (node (ref "R23") (pin "1") (pinfunction "1_1") (pintype "passive"))
      (node (ref "R24") (pin "1") (pinfunction "1_1") (pintype "passive"))
    )
    (net (code "11") (name "Net-(0001001-CH1)") (class "Default")
      (node (ref "0001001") (pin "12") (pinfunction "CH1_12") (pintype "bidirectional"))
      (node (ref "R21") (pin "1") (pinfunction "1_1") (pintype "passive"))
      (node (ref "R22") (pin "1") (pinfunction "1_1") (pintype "passive"))
    )
    (net (code "12") (name "Net-(0001001-CH2)") (class "Default")
      (node (ref "0001001") (pin "13") (pinfunction "CH2_13") (pintype "bidirectional"))
      (node (ref "R19") (pin "1") (pinfunction "1_1") (pintype "passive"))
      (node (ref "R20") (pin "1") (pinfunction "1_1") (pintype "passive"))
    )
    (net (code "13") (name "Net-(0001001-CH3)") (class "Default")
      (node (ref "0001001") (pin "14") (pinfunction "CH3_14") (pintype "bidirectional"))
      (node (ref "R17") (pin "1") (pinfunction "1_1") (pintype "passive"))
      (node (ref "R18") (pin "1") (pinfunction "1_1") (pintype "passive"))
    )
    (net (code "14") (name "Net-(0001001-CH4)") (class "Default")
      (node (ref "0001001") (pin "15") (pinfunction "CH4_15") (pintype "bidirectional"))
      (node (ref "R15") (pin "1") (pinfunction "1_1") (pintype "passive"))
      (node (ref "R16") (pin "1") (pinfunction "1_1") (pintype "passive"))
    )
    (net (code "15") (name "Net-(0001001-CH5)") (class "Default")
      (node (ref "0001001") (pin "16") (pinfunction "CH5_16") (pintype "bidirectional"))
      (node (ref "R13") (pin "1") (pinfunction "1_1") (pintype "passive"))
      (node (ref "R14") (pin "1") (pinfunction "1_1") (pintype "passive"))
    )
    (net (code "16") (name "Net-(0001001-CH6)") (class "Default")
      (node (ref "0001001") (pin "17") (pinfunction "CH6_17") (pintype "bidirectional"))
      (node (ref "R11") (pin "1") (pinfunction "1_1") (pintype "passive"))
      (node (ref "R12") (pin "1") (pinfunction "1_1") (pintype "passive"))
    )
    (net (code "17") (name "Net-(0001001-CH7)") (class "Default")
      (node (ref "0001001") (pin "18") (pinfunction "CH7_18") (pintype "bidirectional"))
      (node (ref "R10") (pin "1") (pinfunction "1_1") (pintype "passive"))
      (node (ref "R9") (pin "1") (pinfunction "1_1") (pintype "passive"))
    )
    (net (code "18") (name "Net-(0001001-REFCOMP)") (class "Default")
      (node (ref "0001001") (pin "1") (pinfunction "REFCOMP_1") (pintype "bidirectional"))
      (node (ref "C10") (pin "1") (pinfunction "1_1") (pintype "passive"))
      (node (ref "C11") (pin "1") (pinfunction "1_1") (pintype "passive"))
    )
    (net (code "19") (name "Net-(0001001-VREF)") (class "Default")
      (node (ref "0001001") (pin "20") (pinfunction "VREF_20") (pintype "bidirectional"))
      (node (ref "C12") (pin "1") (pinfunction "1_1") (pintype "passive"))
    )
    (net (code "20") (name "Net-(0001010-CH0)") (class "Default")
      (node (ref "0001010") (pin "11") (pinfunction "CH0_11") (pintype "bidirectional"))
      (node (ref "R37") (pin "1") (pinfunction "1_1") (pintype "passive"))
      (node (ref "R38") (pin "1") (pinfunction "1_1") (pintype "passive"))
    )
    (net (code "21") (name "Net-(0001010-CH1)") (class "Default")
      (node (ref "0001010") (pin "12") (pinfunction "CH1_12") (pintype "bidirectional"))
      (node (ref "R35") (pin "1") (pinfunction "1_1") (pintype "passive"))
      (node (ref "R36") (pin "1") (pinfunction "1_1") (pintype "passive"))
    )
    (net (code "22") (name "Net-(0001010-CH2)") (class "Default")
      (node (ref "0001010") (pin "13") (pinfunction "CH2_13") (pintype "bidirectional"))
      (node (ref "R33") (pin "1") (pinfunction "1_1") (pintype "passive"))
      (node (ref "R34") (pin "1") (pinfunction "1_1") (pintype "passive"))
    )
    (net (code "23") (name "Net-(0001010-CH3)") (class "Default")
      (node (ref "0001010") (pin "14") (pinfunction "CH3_14") (pintype "bidirectional"))
      (node (ref "R31") (pin "1") (pinfunction "1_1") (pintype "passive"))
      (node (ref "R32") (pin "1") (pinfunction "1_1") (pintype "passive"))
    )
    (net (code "24") (name "Net-(0001010-CH4)") (class "Default")
      (node (ref "0001010") (pin "15") (pinfunction "CH4_15") (pintype "bidirectional"))
      (node (ref "R29") (pin "1") (pinfunction "1_1") (pintype "passive"))
      (node (ref "R30") (pin "1") (pinfunction "1_1") (pintype "passive"))
    )
    (net (code "25") (name "Net-(0001010-CH5)") (class "Default")
      (node (ref "0001010") (pin "16") (pinfunction "CH5_16") (pintype "bidirectional"))
      (node (ref "R27") (pin "1") (pinfunction "1_1") (pintype "passive"))
      (node (ref "R28") (pin "1") (pinfunction "1_1") (pintype "passive"))
    )
    (net (code "26") (name "Net-(0001010-CH6)") (class "Default")
      (node (ref "0001010") (pin "17") (pinfunction "CH6_17") (pintype "bidirectional"))
      (node (ref "R25") (pin "1") (pinfunction "1_1") (pintype "passive"))
      (node (ref "R26") (pin "1") (pinfunction "1_1") (pintype "passive"))
    )
    (net (code "27") (name "Net-(0001010-CH7)") (class "Default")
      (node (ref "0001010") (pin "18") (pinfunction "CH7_18") (pintype "bidirectional"))
      (node (ref "R39") (pin "1") (pinfunction "1_1") (pintype "passive"))
      (node (ref "R40") (pin "1") (pinfunction "1_1") (pintype "passive"))
    )
    (net (code "28") (name "Net-(0001010-REFCOMP)") (class "Default")
      (node (ref "0001010") (pin "1") (pinfunction "REFCOMP_1") (pintype "bidirectional"))
      (node (ref "C13") (pin "1") (pinfunction "1_1") (pintype "passive"))
      (node (ref "C14") (pin "1") (pinfunction "1_1") (pintype "passive"))
    )
    (net (code "29") (name "Net-(0001010-VREF)") (class "Default")
      (node (ref "0001010") (pin "20") (pinfunction "VREF_20") (pintype "bidirectional"))
      (node (ref "C18") (pin "1") (pinfunction "1_1") (pintype "passive"))
    )
    (net (code "30") (name "Net-(0001011-CH0)") (class "Default")
      (node (ref "0001011") (pin "11") (pinfunction "CH0_11") (pintype "bidirectional"))
      (node (ref "R55") (pin "1") (pinfunction "1_1") (pintype "passive"))
      (node (ref "R56") (pin "1") (pinfunction "1_1") (pintype "passive"))
    )
    (net (code "31") (name "Net-(0001011-CH1)") (class "Default")
      (node (ref "0001011") (pin "12") (pinfunction "CH1_12") (pintype "bidirectional"))
      (node (ref "R53") (pin "1") (pinfunction "1_1") (pintype "passive"))
      (node (ref "R54") (pin "1") (pinfunction "1_1") (pintype "passive"))
    )
    (net (code "32") (name "Net-(0001011-CH2)") (class "Default")
      (node (ref "0001011") (pin "13") (pinfunction "CH2_13") (pintype "bidirectional"))
      (node (ref "R51") (pin "1") (pinfunction "1_1") (pintype "passive"))
      (node (ref "R52") (pin "1") (pinfunction "1_1") (pintype "passive"))
    )
    (net (code "33") (name "Net-(0001011-CH3)") (class "Default")
      (node (ref "0001011") (pin "14") (pinfunction "CH3_14") (pintype "bidirectional"))
      (node (ref "R49") (pin "1") (pinfunction "1_1") (pintype "passive"))
      (node (ref "R50") (pin "1") (pinfunction "1_1") (pintype "passive"))
    )
    (net (code "34") (name "Net-(0001011-CH4)") (class "Default")
      (node (ref "0001011") (pin "15") (pinfunction "CH4_15") (pintype "bidirectional"))
      (node (ref "R41") (pin "1") (pinfunction "1_1") (pintype "passive"))
      (node (ref "R42") (pin "1") (pinfunction "1_1") (pintype "passive"))
    )
    (net (code "35") (name "Net-(0001011-CH5)") (class "Default")
      (node (ref "0001011") (pin "16") (pinfunction "CH5_16") (pintype "bidirectional"))
      (node (ref "R43") (pin "1") (pinfunction "1_1") (pintype "passive"))
      (node (ref "R44") (pin "1") (pinfunction "1_1") (pintype "passive"))
    )
    (net (code "36") (name "Net-(0001011-CH6)") (class "Default")
      (node (ref "0001011") (pin "17") (pinfunction "CH6_17") (pintype "bidirectional"))
      (node (ref "R45") (pin "1") (pinfunction "1_1") (pintype "passive"))
      (node (ref "R46") (pin "1") (pinfunction "1_1") (pintype "passive"))
    )
    (net (code "37") (name "Net-(0001011-CH7)") (class "Default")
      (node (ref "0001011") (pin "18") (pinfunction "CH7_18") (pintype "bidirectional"))
      (node (ref "R47") (pin "1") (pinfunction "1_1") (pintype "passive"))
      (node (ref "R48") (pin "1") (pinfunction "1_1") (pintype "passive"))
    )
    (net (code "38") (name "Net-(0001011-REFCOMP)") (class "Default")
      (node (ref "0001011") (pin "1") (pinfunction "REFCOMP_1") (pintype "bidirectional"))
      (node (ref "C19") (pin "1") (pinfunction "1_1") (pintype "passive"))
      (node (ref "C20") (pin "1") (pinfunction "1_1") (pintype "passive"))
    )
    (net (code "39") (name "Net-(0001011-VREF)") (class "Default")
      (node (ref "0001011") (pin "20") (pinfunction "VREF_20") (pintype "bidirectional"))
      (node (ref "C24") (pin "1") (pinfunction "1_1") (pintype "passive"))
    )
    (net (code "40") (name "Net-(0011000-CH0)") (class "Default")
      (node (ref "0011000") (pin "11") (pinfunction "CH0_11") (pintype "bidirectional"))
      (node (ref "R71") (pin "1") (pinfunction "1_1") (pintype "passive"))
      (node (ref "R72") (pin "1") (pinfunction "1_1") (pintype "passive"))
    )
    (net (code "41") (name "Net-(0011000-CH1)") (class "Default")
      (node (ref "0011000") (pin "12") (pinfunction "CH1_12") (pintype "bidirectional"))
      (node (ref "R69") (pin "1") (pinfunction "1_1") (pintype "passive"))
      (node (ref "R70") (pin "1") (pinfunction "1_1") (pintype "passive"))
    )
    (net (code "42") (name "Net-(0011000-CH2)") (class "Default")
      (node (ref "0011000") (pin "13") (pinfunction "CH2_13") (pintype "bidirectional"))
      (node (ref "R67") (pin "1") (pinfunction "1_1") (pintype "passive"))
      (node (ref "R68") (pin "1") (pinfunction "1_1") (pintype "passive"))
    )
    (net (code "43") (name "Net-(0011000-CH3)") (class "Default")
      (node (ref "0011000") (pin "14") (pinfunction "CH3_14") (pintype "bidirectional"))
      (node (ref "R65") (pin "1") (pinfunction "1_1") (pintype "passive"))
      (node (ref "R66") (pin "1") (pinfunction "1_1") (pintype "passive"))
    )
    (net (code "44") (name "Net-(0011000-CH4)") (class "Default")
      (node (ref "0011000") (pin "15") (pinfunction "CH4_15") (pintype "bidirectional"))
      (node (ref "R57") (pin "1") (pinfunction "1_1") (pintype "passive"))
      (node (ref "R58") (pin "1") (pinfunction "1_1") (pintype "passive"))
    )
    (net (code "45") (name "Net-(0011000-CH5)") (class "Default")
      (node (ref "0011000") (pin "16") (pinfunction "CH5_16") (pintype "bidirectional"))
      (node (ref "R59") (pin "1") (pinfunction "1_1") (pintype "passive"))
      (node (ref "R60") (pin "1") (pinfunction "1_1") (pintype "passive"))
    )
    (net (code "46") (name "Net-(0011000-CH6)") (class "Default")
      (node (ref "0011000") (pin "17") (pinfunction "CH6_17") (pintype "bidirectional"))
      (node (ref "R61") (pin "1") (pinfunction "1_1") (pintype "passive"))
      (node (ref "R62") (pin "1") (pinfunction "1_1") (pintype "passive"))
    )
    (net (code "47") (name "Net-(0011000-CH7)") (class "Default")
      (node (ref "0011000") (pin "18") (pinfunction "CH7_18") (pintype "bidirectional"))
      (node (ref "R63") (pin "1") (pinfunction "1_1") (pintype "passive"))
      (node (ref "R64") (pin "1") (pinfunction "1_1") (pintype "passive"))
    )
    (net (code "48") (name "Net-(0011000-REFCOMP)") (class "Default")
      (node (ref "0011000") (pin "1") (pinfunction "REFCOMP_1") (pintype "bidirectional"))
      (node (ref "C25") (pin "1") (pinfunction "1_1") (pintype "passive"))
      (node (ref "C26") (pin "1") (pinfunction "1_1") (pintype "passive"))
    )
    (net (code "49") (name "Net-(0011000-VREF)") (class "Default")
      (node (ref "0011000") (pin "20") (pinfunction "VREF_20") (pintype "bidirectional"))
      (node (ref "C30") (pin "1") (pinfunction "1_1") (pintype "passive"))
    )
    (net (code "50") (name "Net-(0011001-CH0)") (class "Default")
      (node (ref "0011001") (pin "11") (pinfunction "CH0_11") (pintype "bidirectional"))
      (node (ref "R83") (pin "1") (pinfunction "1_1") (pintype "passive"))
      (node (ref "R84") (pin "1") (pinfunction "1_1") (pintype "passive"))
    )
    (net (code "51") (name "Net-(0011001-CH1)") (class "Default")
      (node (ref "0011001") (pin "12") (pinfunction "CH1_12") (pintype "bidirectional"))
      (node (ref "R81") (pin "1") (pinfunction "1_1") (pintype "passive"))
      (node (ref "R82") (pin "1") (pinfunction "1_1") (pintype "passive"))
    )
    (net (code "52") (name "Net-(0011001-CH2)") (class "Default")
      (node (ref "0011001") (pin "13") (pinfunction "CH2_13") (pintype "bidirectional"))
      (node (ref "R79") (pin "1") (pinfunction "1_1") (pintype "passive"))
      (node (ref "R80") (pin "1") (pinfunction "1_1") (pintype "passive"))
    )
    (net (code "53") (name "Net-(0011001-CH3)") (class "Default")
      (node (ref "0011001") (pin "14") (pinfunction "CH3_14") (pintype "bidirectional"))
      (node (ref "R77") (pin "1") (pinfunction "1_1") (pintype "passive"))
      (node (ref "R78") (pin "1") (pinfunction "1_1") (pintype "passive"))
    )
    (net (code "54") (name "Net-(0011001-CH4)") (class "Default")
      (node (ref "0011001") (pin "15") (pinfunction "CH4_15") (pintype "bidirectional"))
      (node (ref "R75") (pin "1") (pinfunction "1_1") (pintype "passive"))
      (node (ref "R76") (pin "1") (pinfunction "1_1") (pintype "passive"))
    )
    (net (code "55") (name "Net-(0011001-CH5)") (class "Default")
      (node (ref "0011001") (pin "16") (pinfunction "CH5_16") (pintype "bidirectional"))
      (node (ref "R73") (pin "1") (pinfunction "1_1") (pintype "passive"))
      (node (ref "R74") (pin "1") (pinfunction "1_1") (pintype "passive"))
    )
    (net (code "56") (name "Net-(0011001-REFCOMP)") (class "Default")
      (node (ref "0011001") (pin "1") (pinfunction "REFCOMP_1") (pintype "bidirectional"))
      (node (ref "C31") (pin "1") (pinfunction "1_1") (pintype "passive"))
      (node (ref "C32") (pin "1") (pinfunction "1_1") (pintype "passive"))
    )
    (net (code "57") (name "Net-(0011001-VREF)") (class "Default")
      (node (ref "0011001") (pin "20") (pinfunction "VREF_20") (pintype "bidirectional"))
      (node (ref "C36") (pin "1") (pinfunction "1_1") (pintype "passive"))
    )
    (net (code "58") (name "Net-(U$1-PCINT6{slash}XTAL1{slash}TOSC1)") (class "Default")
      (node (ref "C39") (pin "1") (pinfunction "1_1") (pintype "passive"))
      (node (ref "U$1") (pin "9") (pinfunction "PCINT6/XTAL1/TOSC1_9") (pintype "bidirectional"))
      (node (ref "Y1") (pin "2") (pinfunction "2_2") (pintype "passive"))
    )
    (net (code "59") (name "Net-(U$1-PCINT7{slash}XTAL2{slash}TOSC2)") (class "Default")
      (node (ref "C40") (pin "1") (pinfunction "1_1") (pintype "passive"))
      (node (ref "U$1") (pin "10") (pinfunction "PCINT7/XTAL2/TOSC2_10") (pintype "bidirectional"))
      (node (ref "Y1") (pin "1") (pinfunction "1_1") (pintype "passive"))
    )
    (net (code "60") (name "Net-(U2-C1+)") (class "Default")
      (node (ref "C43") (pin "1") (pinfunction "1_1") (pintype "passive"))
      (node (ref "U2") (pin "2") (pinfunction "C1+_2") (pintype "passive"))
    )
    (net (code "61") (name "Net-(U2-C1-)") (class "Default")
      (node (ref "C43") (pin "2") (pinfunction "2_2") (pintype "passive"))
      (node (ref "U2") (pin "4") (pinfunction "C1-_4") (pintype "passive"))
    )
    (net (code "62") (name "Net-(U2-C2+)") (class "Default")
      (node (ref "C44") (pin "1") (pinfunction "1_1") (pintype "passive"))
      (node (ref "U2") (pin "5") (pinfunction "C2+_5") (pintype "passive"))
    )
    (net (code "63") (name "Net-(U2-C2-)") (class "Default")
      (node (ref "C44") (pin "2") (pinfunction "2_2") (pintype "passive"))
      (node (ref "U2") (pin "6") (pinfunction "C2-_6") (pintype "passive"))
    )
    (net (code "64") (name "Net-(U2-V+)") (class "Default")
      (node (ref "C41") (pin "1") (pinfunction "1_1") (pintype "passive"))
      (node (ref "U2") (pin "3") (pinfunction "V+_3") (pintype "power_in"))
    )
    (net (code "65") (name "Net-(U2-V-)") (class "Default")
      (node (ref "C42") (pin "1") (pinfunction "1_1") (pintype "passive"))
      (node (ref "U2") (pin "7") (pinfunction "V-_7") (pintype "power_in"))
    )
    (net (code "66") (name "RESET") (class "Default")
      (node (ref "ISP1") (pin "5") (pinfunction "RST_5") (pintype "output"))
      (node (ref "R87") (pin "1") (pinfunction "1_1") (pintype "passive"))
      (node (ref "RESET_BTN") (pin "P$3") (pinfunction "P$2_P$3") (pintype "bidirectional"))
      (node (ref "RESET_BTN") (pin "P$4") (pinfunction "P$2_P$4") (pintype "bidirectional"))
      (node (ref "U$1") (pin "1") (pinfunction "PCINT14/RESET_1") (pintype "bidirectional"))
    )
    (net (code "67") (name "RX") (class "Default")
      (node (ref "TO_FCC") (pin "P$7") (pinfunction "7_P$7") (pintype "bidirectional"))
      (node (ref "U$1") (pin "2") (pinfunction "PCINT16/RXD_2") (pintype "bidirectional"))
      (node (ref "U2") (pin "9") (pinfunction "ROUT_9") (pintype "output"))
    )
    (net (code "68") (name "RX12") (class "Default")
      (node (ref "TO_FCC") (pin "P$2") (pinfunction "2_P$2") (pintype "bidirectional"))
      (node (ref "U2") (pin "8") (pinfunction "RIN_8") (pintype "input"))
    )
    (net (code "69") (name "SCK") (class "Default")
      (node (ref "ISP1") (pin "3") (pinfunction "SCK_3") (pintype "output"))
      (node (ref "U$1") (pin "19") (pinfunction "SCK/PCINT5_19") (pintype "bidirectional"))
    )
    (net (code "70") (name "SCL") (class "Default")
      (node (ref "0001000") (pin "6") (pinfunction "SCL_6") (pintype "bidirectional"))
      (node (ref "0001001") (pin "6") (pinfunction "SCL_6") (pintype "bidirectional"))
      (node (ref "0001010") (pin "6") (pinfunction "SCL_6") (pintype "bidirectional"))
      (node (ref "0001011") (pin "6") (pinfunction "SCL_6") (pintype "bidirectional"))
      (node (ref "0011000") (pin "6") (pinfunction "SCL_6") (pintype "bidirectional"))
      (node (ref "0011001") (pin "6") (pinfunction "SCL_6") (pintype "bidirectional"))
      (node (ref "R85") (pin "1") (pinfunction "1_1") (pintype "passive"))
      (node (ref "U$1") (pin "28") (pinfunction "ADC5/SCL/PCINT13_28") (pintype "bidirectional"))
    )
    (net (code "71") (name "SDA") (class "Default")
      (node (ref "0001000") (pin "7") (pinfunction "SDA_7") (pintype "bidirectional"))
      (node (ref "0001001") (pin "7") (pinfunction "SDA_7") (pintype "bidirectional"))
      (node (ref "0001010") (pin "7") (pinfunction "SDA_7") (pintype "bidirectional"))
      (node (ref "0001011") (pin "7") (pinfunction "SDA_7") (pintype "bidirectional"))
      (node (ref "0011000") (pin "7") (pinfunction "SDA_7") (pintype "bidirectional"))
      (node (ref "0011001") (pin "7") (pinfunction "SDA_7") (pintype "bidirectional"))
      (node (ref "R86") (pin "1") (pinfunction "1_1") (pintype "passive"))
      (node (ref "U$1") (pin "27") (pinfunction "ADC4/SDA/PCINT12_27") (pintype "bidirectional"))
    )
    (net (code "72") (name "SER_INVALID") (class "Default")
      (node (ref "U2") (pin "10") (pinfunction "~{INVALID}_10") (pintype "output"))
    )
    (net (code "73") (name "SIG1") (class "Default")
      (node (ref "TO_FCC") (pin "P$5") (pinfunction "5_P$5") (pintype "bidirectional"))
      (node (ref "U$1") (pin "26") (pinfunction "ADC3/PCINT11_26") (pintype "bidirectional"))
    )
    (net (code "74") (name "SIG2") (class "Default")
      (node (ref "TO_FCC") (pin "P$6") (pinfunction "6_P$6") (pintype "bidirectional"))
      (node (ref "U$1") (pin "25") (pinfunction "ADC2/PCINT10_25") (pintype "bidirectional"))
    )
    (net (code "75") (name "TX") (class "Default")
      (node (ref "TO_FCC") (pin "P$8") (pinfunction "8_P$8") (pintype "bidirectional"))
      (node (ref "U$1") (pin "3") (pinfunction "PCINT17/TXD_3") (pintype "bidirectional"))
      (node (ref "U2") (pin "11") (pinfunction "DIN_11") (pintype "input"))
    )
    (net (code "76") (name "TX12") (class "Default")
      (node (ref "TO_FCC") (pin "P$3") (pinfunction "3_P$3") (pintype "bidirectional"))
      (node (ref "U2") (pin "13") (pinfunction "DOUT_13") (pintype "output"))
    )
    (net (code "77") (name "V+") (class "Default")
      (node (ref "0001000") (pin "10") (pinfunction "VDD1_10") (pintype "bidirectional"))
      (node (ref "0001000") (pin "3") (pinfunction "VDD0_3") (pintype "bidirectional"))
      (node (ref "0001001") (pin "10") (pinfunction "VDD1_10") (pintype "bidirectional"))
      (node (ref "0001001") (pin "3") (pinfunction "VDD0_3") (pintype "bidirectional"))
      (node (ref "0001010") (pin "10") (pinfunction "VDD1_10") (pintype "bidirectional"))
      (node (ref "0001010") (pin "3") (pinfunction "VDD0_3") (pintype "bidirectional"))
      (node (ref "0001010") (pin "4") (pinfunction "AD0_4") (pintype "bidirectional"))
      (node (ref "0001011") (pin "10") (pinfunction "VDD1_10") (pintype "bidirectional"))
      (node (ref "0001011") (pin "3") (pinfunction "VDD0_3") (pintype "bidirectional"))
      (node (ref "0001011") (pin "4") (pinfunction "AD0_4") (pintype "bidirectional"))
      (node (ref "0011000") (pin "10") (pinfunction "VDD1_10") (pintype "bidirectional"))
      (node (ref "0011000") (pin "3") (pinfunction "VDD0_3") (pintype "bidirectional"))
      (node (ref "0011001") (pin "10") (pinfunction "VDD1_10") (pintype "bidirectional"))
      (node (ref "0011001") (pin "3") (pinfunction "VDD0_3") (pintype "bidirectional"))
      (node (ref "C1") (pin "1") (pinfunction "1_1") (pintype "passive"))
      (node (ref "C15") (pin "1") (pinfunction "1_1") (pintype "passive"))
      (node (ref "C16") (pin "1") (pinfunction "1_1") (pintype "passive"))
      (node (ref "C17") (pin "1") (pinfunction "1_1") (pintype "passive"))
      (node (ref "C2") (pin "1") (pinfunction "1_1") (pintype "passive"))
      (node (ref "C21") (pin "1") (pinfunction "1_1") (pintype "passive"))
      (node (ref "C22") (pin "1") (pinfunction "1_1") (pintype "passive"))
      (node (ref "C23") (pin "1") (pinfunction "1_1") (pintype "passive"))
      (node (ref "C27") (pin "1") (pinfunction "1_1") (pintype "passive"))
      (node (ref "C28") (pin "1") (pinfunction "1_1") (pintype "passive"))
      (node (ref "C29") (pin "1") (pinfunction "1_1") (pintype "passive"))
      (node (ref "C3") (pin "1") (pinfunction "1_1") (pintype "passive"))
      (node (ref "C33") (pin "1") (pinfunction "1_1") (pintype "passive"))
      (node (ref "C34") (pin "1") (pinfunction "1_1") (pintype "passive"))
      (node (ref "C35") (pin "1") (pinfunction "1_1") (pintype "passive"))
      (node (ref "C37") (pin "1") (pinfunction "1_1") (pintype "passive"))
      (node (ref "C38") (pin "1") (pinfunction "1_1") (pintype "passive"))
      (node (ref "C7") (pin "1") (pinfunction "1_1") (pintype "passive"))
      (node (ref "C8") (pin "1") (pinfunction "1_1") (pintype "passive"))
      (node (ref "C9") (pin "1") (pinfunction "1_1") (pintype "passive"))
      (node (ref "ISP1") (pin "2") (pinfunction "VCC_2") (pintype "power_in"))
      (node (ref "R85") (pin "2") (pinfunction "2_2") (pintype "passive"))
      (node (ref "R86") (pin "2") (pinfunction "2_2") (pintype "passive"))
      (node (ref "R87") (pin "2") (pinfunction "2_2") (pintype "passive"))
      (node (ref "TO_FCC") (pin "P$1") (pinfunction "1_P$1") (pintype "bidirectional"))
      (node (ref "U$1") (pin "20") (pinfunction "AVCC_20") (pintype "bidirectional"))
      (node (ref "U$1") (pin "7") (pinfunction "VCC_7") (pintype "bidirectional"))
      (node (ref "U2") (pin "15") (pinfunction "VCC_15") (pintype "power_in"))
      (node (ref "U2") (pin "16") (pinfunction "~{FORCEOFF}_16") (pintype "input"))
    )
    (net (code "78") (name "V1") (class "Default")
      (node (ref "0001000") (pin "11") (pinfunction "CH0_11") (pintype "bidirectional"))
      (node (ref "R91") (pin "2") (pinfunction "2_2") (pintype "passive"))
      (node (ref "U$3") (pin "1") (pinfunction "1_1") (pintype "bidirectional"))
    )
    (net (code "79") (name "V2") (class "Default")
      (node (ref "0001000") (pin "12") (pinfunction "CH1_12") (pintype "bidirectional"))
      (node (ref "R90") (pin "2") (pinfunction "2_2") (pintype "passive"))
      (node (ref "U$3") (pin "2") (pinfunction "2_2") (pintype "bidirectional"))
    )
    (net (code "80") (name "V3") (class "Default")
      (node (ref "0001000") (pin "13") (pinfunction "CH2_13") (pintype "bidirectional"))
      (node (ref "R89") (pin "2") (pinfunction "2_2") (pintype "passive"))
      (node (ref "U$3") (pin "3") (pinfunction "3_3") (pintype "bidirectional"))
    )
    (net (code "81") (name "V4") (class "Default")
      (node (ref "0001000") (pin "14") (pinfunction "CH3_14") (pintype "bidirectional"))
      (node (ref "R88") (pin "2") (pinfunction "2_2") (pintype "passive"))
      (node (ref "U$3") (pin "4") (pinfunction "4_4") (pintype "bidirectional"))
    )
    (net (code "82") (name "V5") (class "Default")
      (node (ref "R2") (pin "2") (pinfunction "2_2") (pintype "passive"))
      (node (ref "U$3") (pin "5") (pinfunction "5_5") (pintype "bidirectional"))
    )
    (net (code "83") (name "V6") (class "Default")
      (node (ref "R4") (pin "2") (pinfunction "2_2") (pintype "passive"))
      (node (ref "U$3") (pin "6") (pinfunction "6_6") (pintype "bidirectional"))
    )
    (net (code "84") (name "V7") (class "Default")
      (node (ref "R6") (pin "2") (pinfunction "2_2") (pintype "passive"))
      (node (ref "U$3") (pin "7") (pinfunction "7_7") (pintype "bidirectional"))
    )
    (net (code "85") (name "V8") (class "Default")
      (node (ref "R8") (pin "2") (pinfunction "2_2") (pintype "passive"))
      (node (ref "U$3") (pin "8") (pinfunction "8_8") (pintype "bidirectional"))
    )
    (net (code "86") (name "V9") (class "Default")
      (node (ref "R23") (pin "2") (pinfunction "2_2") (pintype "passive"))
      (node (ref "U$3") (pin "9") (pinfunction "9_9") (pintype "bidirectional"))
    )
    (net (code "87") (name "V10") (class "Default")
      (node (ref "R21") (pin "2") (pinfunction "2_2") (pintype "passive"))
      (node (ref "U$3") (pin "10") (pinfunction "10_10") (pintype "bidirectional"))
    )
    (net (code "88") (name "V11") (class "Default")
      (node (ref "R19") (pin "2") (pinfunction "2_2") (pintype "passive"))
      (node (ref "U$3") (pin "11") (pinfunction "11_11") (pintype "bidirectional"))
    )
    (net (code "89") (name "V12") (class "Default")
      (node (ref "R17") (pin "2") (pinfunction "2_2") (pintype "passive"))
      (node (ref "U$3") (pin "12") (pinfunction "12_12") (pintype "bidirectional"))
    )
    (net (code "90") (name "V13") (class "Default")
      (node (ref "R15") (pin "2") (pinfunction "2_2") (pintype "passive"))
      (node (ref "U$3") (pin "13") (pinfunction "13_13") (pintype "bidirectional"))
    )
    (net (code "91") (name "V14") (class "Default")
      (node (ref "R13") (pin "2") (pinfunction "2_2") (pintype "passive"))
      (node (ref "U$3") (pin "14") (pinfunction "14_14") (pintype "bidirectional"))
    )
    (net (code "92") (name "V15") (class "Default")
      (node (ref "R11") (pin "2") (pinfunction "2_2") (pintype "passive"))
      (node (ref "U$3") (pin "15") (pinfunction "15_15") (pintype "bidirectional"))
    )
    (net (code "93") (name "V16") (class "Default")
      (node (ref "R9") (pin "2") (pinfunction "2_2") (pintype "passive"))
      (node (ref "U$3") (pin "16") (pinfunction "16_16") (pintype "bidirectional"))
    )
    (net (code "94") (name "V17") (class "Default")
      (node (ref "R37") (pin "2") (pinfunction "2_2") (pintype "passive"))
      (node (ref "U$3") (pin "17") (pinfunction "17_17") (pintype "bidirectional"))
    )
    (net (code "95") (name "V18") (class "Default")
      (node (ref "R35") (pin "2") (pinfunction "2_2") (pintype "passive"))
      (node (ref "U$3") (pin "18") (pinfunction "18_18") (pintype "bidirectional"))
    )
    (net (code "96") (name "V19") (class "Default")
      (node (ref "R33") (pin "2") (pinfunction "2_2") (pintype "passive"))
      (node (ref "U$3") (pin "19") (pinfunction "19_19") (pintype "bidirectional"))
    )
    (net (code "97") (name "V20") (class "Default")
      (node (ref "R31") (pin "2") (pinfunction "2_2") (pintype "passive"))
      (node (ref "U$3") (pin "20") (pinfunction "20_20") (pintype "bidirectional"))
    )
    (net (code "98") (name "V21") (class "Default")
      (node (ref "R29") (pin "2") (pinfunction "2_2") (pintype "passive"))
      (node (ref "U$3") (pin "21") (pinfunction "21_21") (pintype "bidirectional"))
    )
    (net (code "99") (name "V22") (class "Default")
      (node (ref "R27") (pin "2") (pinfunction "2_2") (pintype "passive"))
      (node (ref "U$3") (pin "22") (pinfunction "22_22") (pintype "bidirectional"))
    )
    (net (code "100") (name "V23") (class "Default")
      (node (ref "R25") (pin "2") (pinfunction "2_2") (pintype "passive"))
      (node (ref "U$3") (pin "23") (pinfunction "23_23") (pintype "bidirectional"))
    )
    (net (code "101") (name "V24") (class "Default")
      (node (ref "R40") (pin "2") (pinfunction "2_2") (pintype "passive"))
      (node (ref "U$3") (pin "24") (pinfunction "24_24") (pintype "bidirectional"))
    )
    (net (code "102") (name "V25") (class "Default")
      (node (ref "R55") (pin "2") (pinfunction "2_2") (pintype "passive"))
      (node (ref "U$3") (pin "25") (pinfunction "25_25") (pintype "bidirectional"))
    )
    (net (code "103") (name "V26") (class "Default")
      (node (ref "R53") (pin "2") (pinfunction "2_2") (pintype "passive"))
      (node (ref "U$3") (pin "26") (pinfunction "26_26") (pintype "bidirectional"))
    )
    (net (code "104") (name "V27") (class "Default")
      (node (ref "R51") (pin "2") (pinfunction "2_2") (pintype "passive"))
      (node (ref "U$3") (pin "27") (pinfunction "27_27") (pintype "bidirectional"))
    )
    (net (code "105") (name "V28") (class "Default")
      (node (ref "R49") (pin "2") (pinfunction "2_2") (pintype "passive"))
      (node (ref "U$3") (pin "28") (pinfunction "28_28") (pintype "bidirectional"))
    )
    (net (code "106") (name "V29") (class "Default")
      (node (ref "R42") (pin "2") (pinfunction "2_2") (pintype "passive"))
      (node (ref "U$3") (pin "29") (pinfunction "29_29") (pintype "bidirectional"))
    )
    (net (code "107") (name "V30") (class "Default")
      (node (ref "R44") (pin "2") (pinfunction "2_2") (pintype "passive"))
      (node (ref "U$3") (pin "30") (pinfunction "30_30") (pintype "bidirectional"))
    )
    (net (code "108") (name "V31") (class "Default")
      (node (ref "R46") (pin "2") (pinfunction "2_2") (pintype "passive"))
      (node (ref "U$3") (pin "31") (pinfunction "31_31") (pintype "bidirectional"))
    )
    (net (code "109") (name "V32") (class "Default")
      (node (ref "R48") (pin "2") (pinfunction "2_2") (pintype "passive"))
      (node (ref "U$3") (pin "32") (pinfunction "32_32") (pintype "bidirectional"))
    )
    (net (code "110") (name "V33") (class "Default")
      (node (ref "R71") (pin "2") (pinfunction "2_2") (pintype "passive"))
      (node (ref "U$3") (pin "33") (pinfunction "33_33") (pintype "bidirectional"))
    )
    (net (code "111") (name "V34") (class "Default")
      (node (ref "R69") (pin "2") (pinfunction "2_2") (pintype "passive"))
      (node (ref "U$3") (pin "34") (pinfunction "34_34") (pintype "bidirectional"))
    )
    (net (code "112") (name "V35") (class "Default")
      (node (ref "R67") (pin "2") (pinfunction "2_2") (pintype "passive"))
      (node (ref "U$3") (pin "35") (pinfunction "35_35") (pintype "bidirectional"))
    )
    (net (code "113") (name "V36") (class "Default")
      (node (ref "R65") (pin "2") (pinfunction "2_2") (pintype "passive"))
      (node (ref "U$3") (pin "36") (pinfunction "36_36") (pintype "bidirectional"))
    )
    (net (code "114") (name "V37") (class "Default")
      (node (ref "R58") (pin "2") (pinfunction "2_2") (pintype "passive"))
      (node (ref "U$3") (pin "37") (pinfunction "37_37") (pintype "bidirectional"))
    )
    (net (code "115") (name "V38") (class "Default")
      (node (ref "R60") (pin "2") (pinfunction "2_2") (pintype "passive"))
      (node (ref "U$3") (pin "38") (pinfunction "38_38") (pintype "bidirectional"))
    )
    (net (code "116") (name "V39") (class "Default")
      (node (ref "R62") (pin "2") (pinfunction "2_2") (pintype "passive"))
      (node (ref "U$3") (pin "39") (pinfunction "39_39") (pintype "bidirectional"))
    )
    (net (code "117") (name "V40") (class "Default")
      (node (ref "R64") (pin "2") (pinfunction "2_2") (pintype "passive"))
      (node (ref "U$3") (pin "40") (pinfunction "40_40") (pintype "bidirectional"))
    )
    (net (code "118") (name "V41") (class "Default")
      (node (ref "R83") (pin "2") (pinfunction "2_2") (pintype "passive"))
      (node (ref "U$3") (pin "41") (pinfunction "41_41") (pintype "bidirectional"))
    )
    (net (code "119") (name "V42") (class "Default")
      (node (ref "R81") (pin "2") (pinfunction "2_2") (pintype "passive"))
      (node (ref "U$3") (pin "42") (pinfunction "42_42") (pintype "bidirectional"))
    )
    (net (code "120") (name "V43") (class "Default")
      (node (ref "R79") (pin "2") (pinfunction "2_2") (pintype "passive"))
      (node (ref "U$3") (pin "43") (pinfunction "43_43") (pintype "bidirectional"))
    )
    (net (code "121") (name "V44") (class "Default")
      (node (ref "R77") (pin "2") (pinfunction "2_2") (pintype "passive"))
      (node (ref "U$3") (pin "44") (pinfunction "44_44") (pintype "bidirectional"))
    )
    (net (code "122") (name "V45") (class "Default")
      (node (ref "R75") (pin "2") (pinfunction "2_2") (pintype "passive"))
      (node (ref "U$3") (pin "45") (pinfunction "45_45") (pintype "bidirectional"))
    )
    (net (code "123") (name "V46") (class "Default")
      (node (ref "R73") (pin "2") (pinfunction "2_2") (pintype "passive"))
      (node (ref "U$3") (pin "46") (pinfunction "46_46") (pintype "bidirectional"))
    )
    (net (code "124") (name "unconnected-(0001001-AD0-Pad4)") (class "Default")
      (node (ref "0001001") (pin "4") (pinfunction "AD0_4") (pintype "bidirectional"))
    )
    (net (code "125") (name "unconnected-(0001011-AD1-Pad5)") (class "Default")
      (node (ref "0001011") (pin "5") (pinfunction "AD1_5") (pintype "bidirectional"))
    )
    (net (code "126") (name "unconnected-(0011000-AD0-Pad4)") (class "Default")
      (node (ref "0011000") (pin "4") (pinfunction "AD0_4") (pintype "bidirectional"))
    )
    (net (code "127") (name "unconnected-(0011000-AD1-Pad5)") (class "Default")
      (node (ref "0011000") (pin "5") (pinfunction "AD1_5") (pintype "bidirectional"))
    )
    (net (code "128") (name "unconnected-(0011001-AD1-Pad5)") (class "Default")
      (node (ref "0011001") (pin "5") (pinfunction "AD1_5") (pintype "bidirectional"))
    )
    (net (code "129") (name "unconnected-(0011001-CH6-Pad17)") (class "Default")
      (node (ref "0011001") (pin "17") (pinfunction "CH6_17") (pintype "bidirectional"))
    )
    (net (code "130") (name "unconnected-(0011001-CH7-Pad18)") (class "Default")
      (node (ref "0011001") (pin "18") (pinfunction "CH7_18") (pintype "bidirectional"))
    )
    (net (code "131") (name "unconnected-(TO_FCC-LED1N-PadP$9)") (class "Default")
      (node (ref "TO_FCC") (pin "P$9") (pinfunction "LED1N_P$9") (pintype "bidirectional"))
    )
    (net (code "132") (name "unconnected-(TO_FCC-LED1P-PadP$10)") (class "Default")
      (node (ref "TO_FCC") (pin "P$10") (pinfunction "LED1P_P$10") (pintype "bidirectional"))
    )
    (net (code "133") (name "unconnected-(TO_FCC-LED2N-PadP$11)") (class "Default")
      (node (ref "TO_FCC") (pin "P$11") (pinfunction "LED2N_P$11") (pintype "bidirectional"))
    )
    (net (code "134") (name "unconnected-(TO_FCC-LED2P-PadP$12)") (class "Default")
      (node (ref "TO_FCC") (pin "P$12") (pinfunction "LED2P_P$12") (pintype "bidirectional"))
    )
    (net (code "135") (name "unconnected-(U$1-ADC0{slash}PCINT8-Pad23)") (class "Default")
      (node (ref "U$1") (pin "23") (pinfunction "ADC0/PCINT8_23") (pintype "bidirectional"))
    )
    (net (code "136") (name "unconnected-(U$1-ADC1{slash}PCINT9-Pad24)") (class "Default")
      (node (ref "U$1") (pin "24") (pinfunction "ADC1/PCINT9_24") (pintype "bidirectional"))
    )
    (net (code "137") (name "unconnected-(U$1-AREF-Pad21)") (class "Default")
      (node (ref "U$1") (pin "21") (pinfunction "AREF_21") (pintype "bidirectional"))
    )
    (net (code "138") (name "unconnected-(U$1-OC1A{slash}PCINT1-Pad15)") (class "Default")
      (node (ref "U$1") (pin "15") (pinfunction "OC1A/PCINT1_15") (pintype "bidirectional"))
    )
    (net (code "139") (name "unconnected-(U$1-PCINT0{slash}CLKO{slash}ICP1-Pad14)") (class "Default")
      (node (ref "U$1") (pin "14") (pinfunction "PCINT0/CLKO/ICP1_14") (pintype "bidirectional"))
    )
    (net (code "140") (name "unconnected-(U$1-PCINT18{slash}INT0-Pad4)") (class "Default")
      (node (ref "U$1") (pin "4") (pinfunction "PCINT18/INT0_4") (pintype "bidirectional"))
    )
    (net (code "141") (name "unconnected-(U$1-PCINT19{slash}OC2B{slash}INT1-Pad5)") (class "Default")
      (node (ref "U$1") (pin "5") (pinfunction "PCINT19/OC2B/INT1_5") (pintype "bidirectional"))
    )
    (net (code "142") (name "unconnected-(U$1-PCINT20{slash}XCK{slash}T0-Pad6)") (class "Default")
      (node (ref "U$1") (pin "6") (pinfunction "PCINT20/XCK/T0_6") (pintype "bidirectional"))
    )
    (net (code "143") (name "unconnected-(U$1-PCINT21{slash}OC0B{slash}T1-Pad11)") (class "Default")
      (node (ref "U$1") (pin "11") (pinfunction "PCINT21/OC0B/T1_11") (pintype "bidirectional"))
    )
    (net (code "144") (name "unconnected-(U$1-PCINT22{slash}OC0A{slash}AIN0-Pad12)") (class "Default")
      (node (ref "U$1") (pin "12") (pinfunction "PCINT22/OC0A/AIN0_12") (pintype "bidirectional"))
    )
    (net (code "145") (name "unconnected-(U$1-PCINT23{slash}AIN1-Pad13)") (class "Default")
      (node (ref "U$1") (pin "13") (pinfunction "PCINT23/AIN1_13") (pintype "bidirectional"))
    )
    (net (code "146") (name "unconnected-(U$1-SS{slash}OC1B{slash}PCINT2-Pad16)") (class "Default")
      (node (ref "U$1") (pin "16") (pinfunction "SS/OC1B/PCINT2_16") (pintype "bidirectional"))
    )
    (net (code "147") (name "unconnected-(U$3-Pad48)") (class "Default")
      (node (ref "U$3") (pin "48") (pinfunction "48_48") (pintype "bidirectional"))
    )
  )
)
